# Interface.net
KiCad netlist of a schematic drawn in Altium Designer
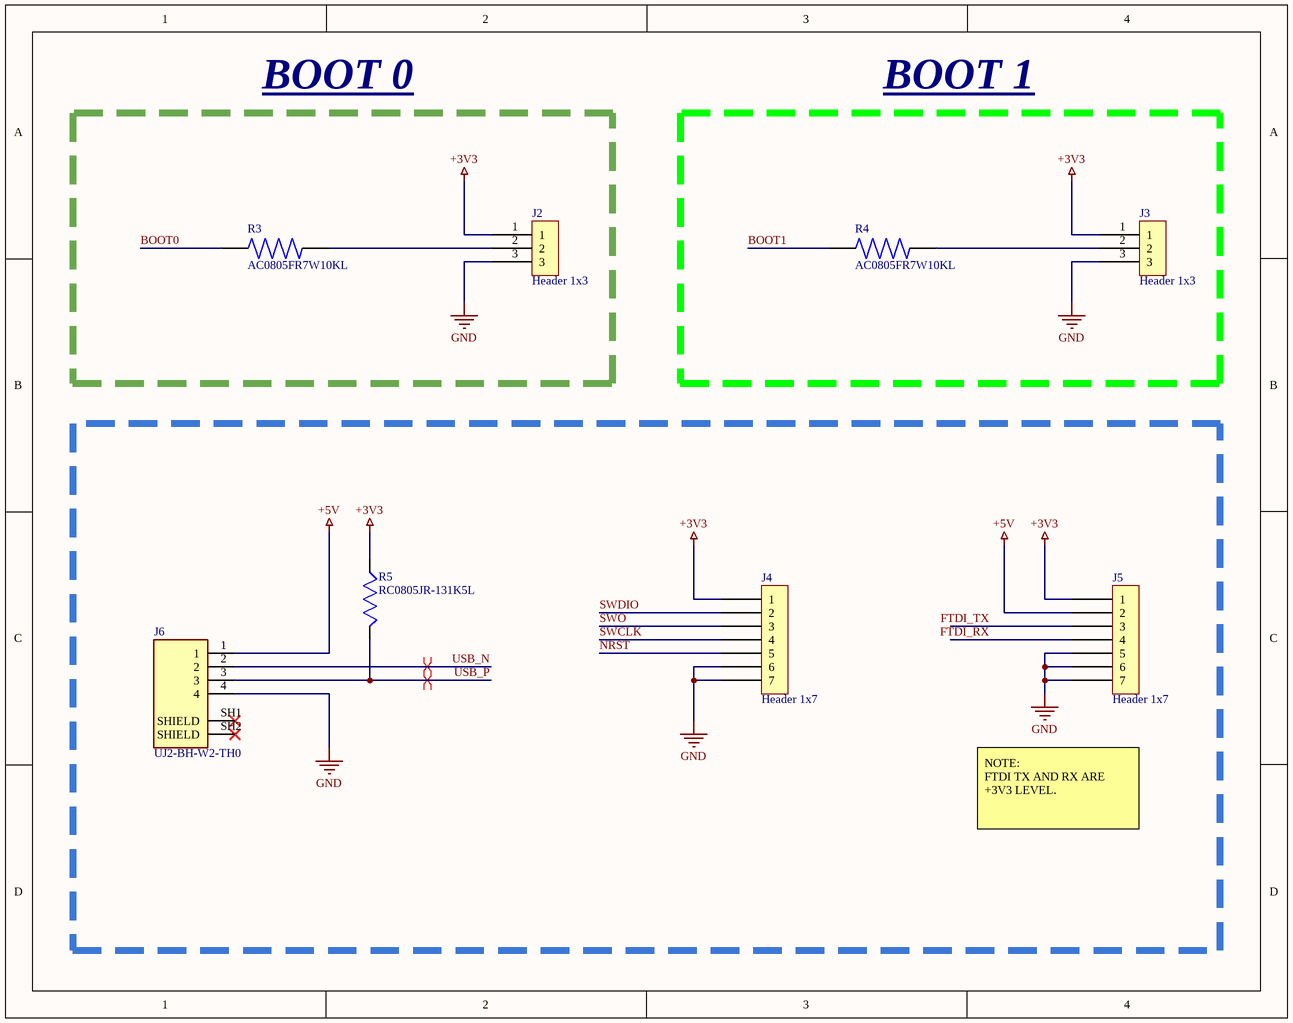
[diagram p0: Interface.SchDoc]

(export (version "E")
  (design (tool "Eeschema 10.0.6"))
  (components
    (comp (ref "J2")
      (value "Header 1x3")
      (footprint "Header 1x3 male")
      (libsource (lib "Headers") (part "Header 1x3"))
    )
    (comp (ref "J3")
      (value "Header 1x3")
      (footprint "Header 1x3 male")
      (libsource (lib "Headers") (part "Header 1x3"))
    )
    (comp (ref "J4")
      (value "Header 1x7")
      (footprint "Header 1x7 male")
      (libsource (lib "Headers") (part "Header 1x7"))
    )
    (comp (ref "J5")
      (value "Header 1x7")
      (footprint "Header 1x7 male")
      (libsource (lib "Headers") (part "Header 1x7"))
    )
    (comp (ref "J6")
      (value "UJ2-BH-W2-TH0")
      (footprint "UJ2-BH-W2-TH0")
      (description "6 Âµin Plating Thickness, White Insulator, USB Receptacle")
      (fields (field (name "MF") "{'manufacturer': u'CUI Devices'}") (field (name "MP") "UJ2-BH-W2-TH"))
      (libsource (lib "UJ2-BH-W2-TH0") (part "UJ2-BH-W2-TH0"))
    )
    (comp (ref "R3")
      (value "AC0805FR7W10KL")
      (footprint "AC0805FR7W10KL:RESC2012X60N")
      (description "RES SMD 18 OHM 5% 1/8W 0805")
      (fields (field (name "MF") "{'manufacturer': u'Yageo Corporation'}"))
      (libsource (lib "*") (part "AC0805FR7W10KL"))
    )
    (comp (ref "R4")
      (value "AC0805FR7W10KL")
      (footprint "AC0805FR7W10KL:RESC2012X60N")
      (description "RES SMD 18 OHM 5% 1/8W 0805")
      (fields (field (name "MF") "{'manufacturer': u'Yageo Corporation'}"))
      (libsource (lib "*") (part "AC0805FR7W10KL"))
    )
    (comp (ref "R5")
      (value "RC0805JR-131K5L")
      (footprint "RC0805JR-131K5L:RESC2012X60N")
      (fields (field (name "MF") "{'manufacturer': u'Yageo'}"))
      (libsource (lib "*") (part "RC0805JR-131K5L"))
    )
  )
  (nets
    (net (code "1") (name "+3V3") (class "Default")
      (node (ref "J2") (pin "1") (pinfunction "1_1") (pintype "passive"))
      (node (ref "J3") (pin "1") (pinfunction "1_1") (pintype "passive"))
      (node (ref "J4") (pin "1") (pinfunction "1_1") (pintype "passive"))
      (node (ref "J5") (pin "1") (pinfunction "1_1") (pintype "passive"))
      (node (ref "R5") (pin "2") (pinfunction "2_2") (pintype "passive"))
    )
    (net (code "2") (name "+5V") (class "Default")
      (node (ref "J5") (pin "2") (pinfunction "2_2") (pintype "passive"))
      (node (ref "J6") (pin "1") (pinfunction "1_1") (pintype "passive"))
    )
    (net (code "3") (name "/BOOT0") (class "Default")
      (node (ref "R3") (pin "1") (pinfunction "1_1") (pintype "passive"))
    )
    (net (code "4") (name "/BOOT1") (class "Default")
      (node (ref "R4") (pin "1") (pinfunction "1_1") (pintype "passive"))
    )
    (net (code "5") (name "/FTDI_RX") (class "Default")
      (node (ref "J5") (pin "4") (pinfunction "4_4") (pintype "passive"))
    )
    (net (code "6") (name "/FTDI_TX") (class "Default")
      (node (ref "J5") (pin "3") (pinfunction "3_3") (pintype "passive"))
    )
    (net (code "7") (name "/NRST") (class "Default")
      (node (ref "J4") (pin "5") (pinfunction "5_5") (pintype "passive"))
    )
    (net (code "8") (name "/SWCLK") (class "Default")
      (node (ref "J4") (pin "4") (pinfunction "4_4") (pintype "passive"))
    )
    (net (code "9") (name "/SWDIO") (class "Default")
      (node (ref "J4") (pin "2") (pinfunction "2_2") (pintype "passive"))
    )
    (net (code "10") (name "/SWO") (class "Default")
      (node (ref "J4") (pin "3") (pinfunction "3_3") (pintype "passive"))
    )
    (net (code "11") (name "/USB_N") (class "Default")
      (node (ref "J6") (pin "2") (pinfunction "2_2") (pintype "passive"))
    )
    (net (code "12") (name "/USB_P") (class "Default")
      (node (ref "J6") (pin "3") (pinfunction "3_3") (pintype "passive"))
      (node (ref "R5") (pin "1") (pinfunction "1_1") (pintype "passive"))
    )
    (net (code "13") (name "GND") (class "Default")
      (node (ref "J2") (pin "3") (pinfunction "3_3") (pintype "passive"))
      (node (ref "J3") (pin "3") (pinfunction "3_3") (pintype "passive"))
      (node (ref "J4") (pin "6") (pinfunction "6_6") (pintype "passive"))
      (node (ref "J4") (pin "7") (pinfunction "7_7") (pintype "passive"))
      (node (ref "J5") (pin "5") (pinfunction "5_5") (pintype "passive"))
      (node (ref "J5") (pin "6") (pinfunction "6_6") (pintype "passive"))
      (node (ref "J5") (pin "7") (pinfunction "7_7") (pintype "passive"))
      (node (ref "J6") (pin "4") (pinfunction "4_4") (pintype "passive"))
    )
    (net (code "14") (name "Net-(J2-Pad2)") (class "Default")
      (node (ref "J2") (pin "2") (pinfunction "2_2") (pintype "passive"))
      (node (ref "R3") (pin "2") (pinfunction "2_2") (pintype "passive"))
    )
    (net (code "15") (name "Net-(J3-Pad2)") (class "Default")
      (node (ref "J3") (pin "2") (pinfunction "2_2") (pintype "passive"))
      (node (ref "R4") (pin "2") (pinfunction "2_2") (pintype "passive"))
    )
    (net (code "16") (name "unconnected-(J6-SHIELD-PadSH1)") (class "Default")
      (node (ref "J6") (pin "SH1") (pinfunction "SHIELD_SH1") (pintype "passive+no_connect"))
    )
    (net (code "17") (name "unconnected-(J6-SHIELD-PadSH2)") (class "Default")
      (node (ref "J6") (pin "SH2") (pinfunction "SHIELD_SH2") (pintype "passive+no_connect"))
    )
  )
)
